# Sania_SCH.net
KiCad netlist of a schematic drawn in EAGLE
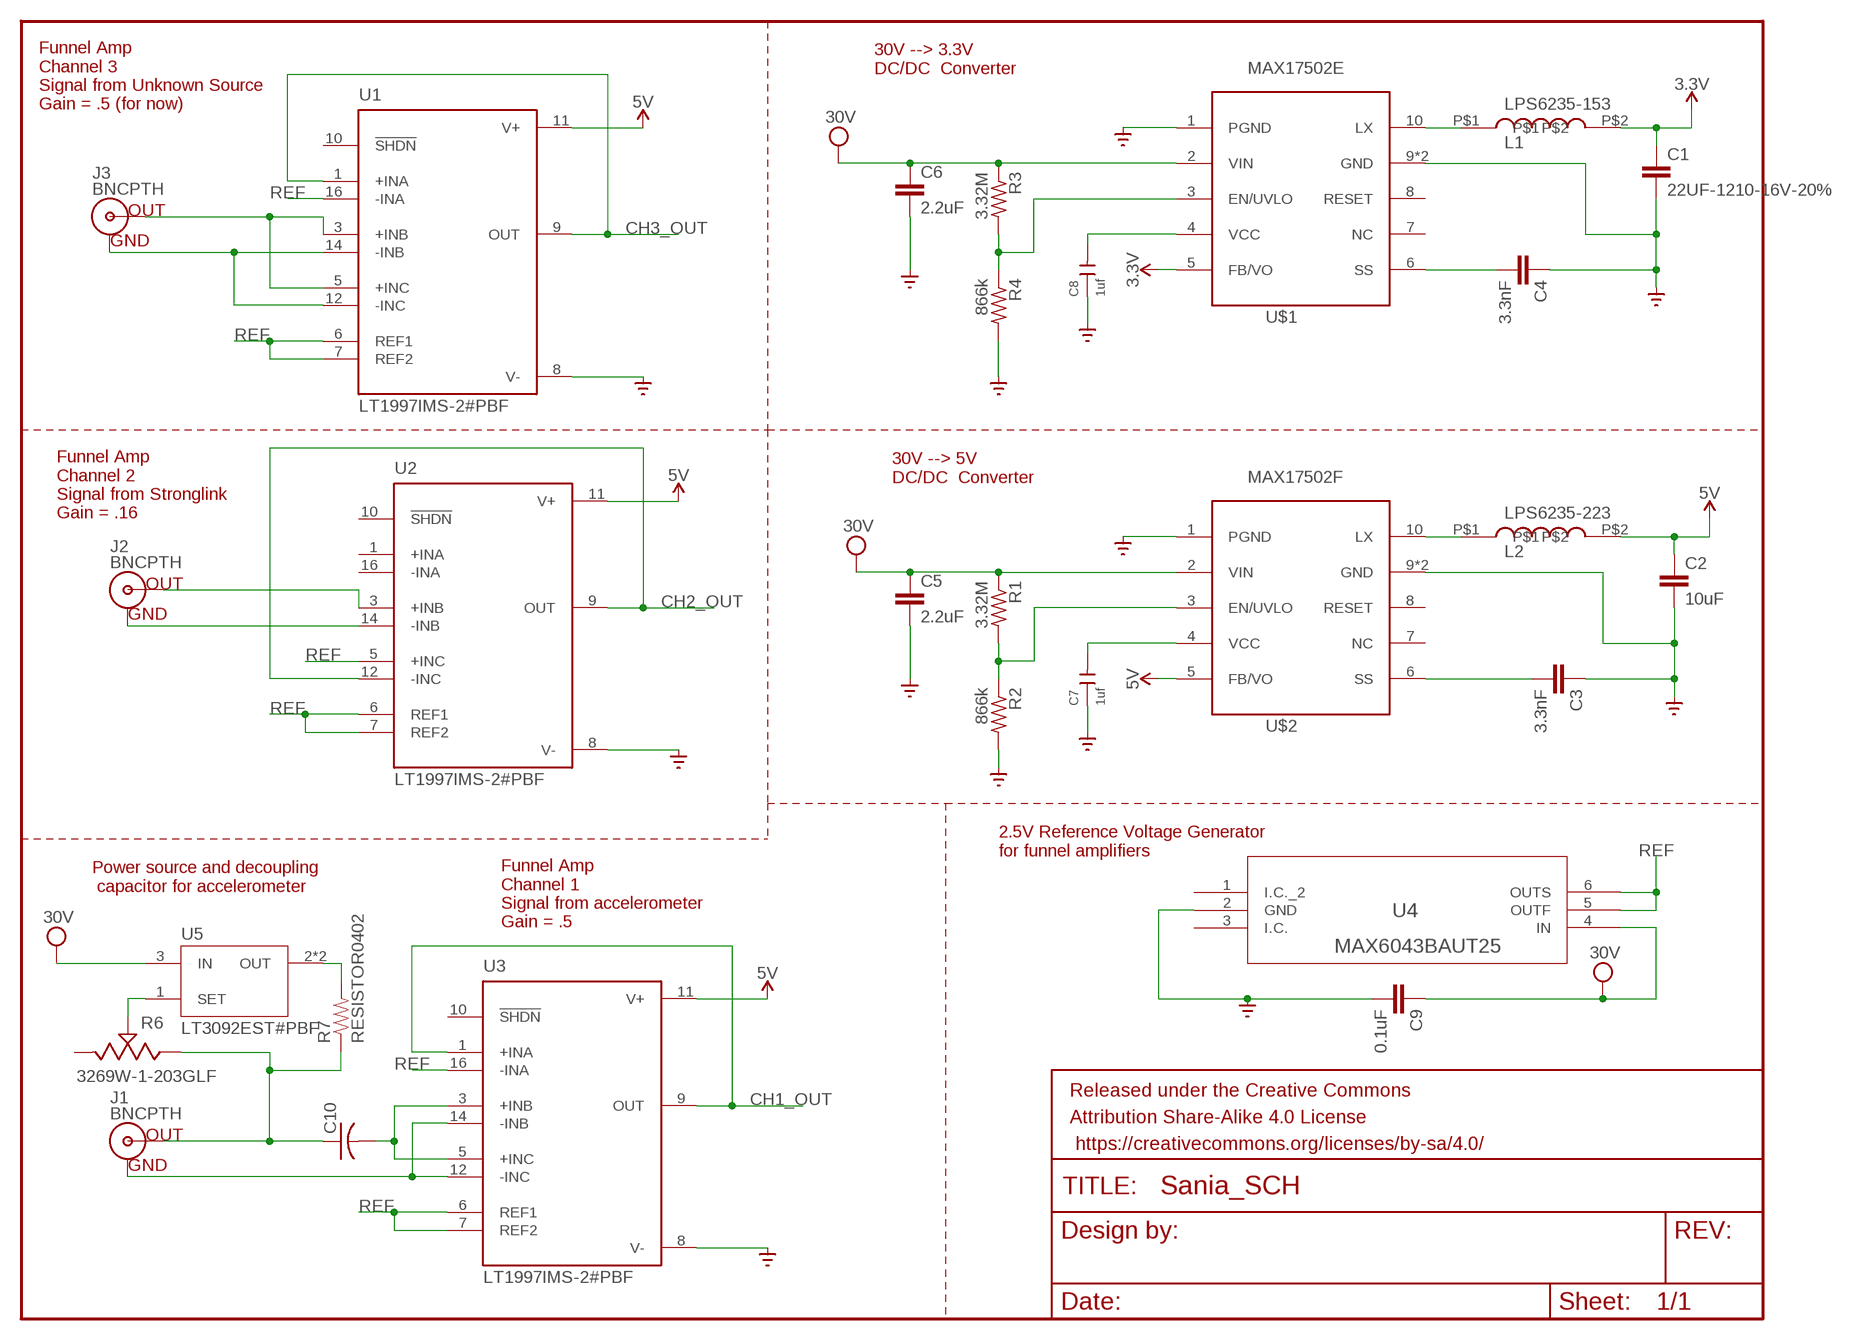
[diagram p0: schematic, sheet 1]

(export (version "E")
  (design (tool "Eeschema 10.0.6"))
  (components
    (comp (ref "C1")
      (value "22UF-1210-16V-20%")
      (footprint "eagle-import:1210")
      (libsource (lib "eagle-import") (part "22UF-1210-16V-20%"))
    )
    (comp (ref "C2")
      (value "10uF")
      (footprint "eagle-import:1210")
      (libsource (lib "eagle-import") (part "10UF-1210-50V-20%"))
    )
    (comp (ref "C3")
      (value "3.3nF")
      (footprint "eagle-import:0603")
      (libsource (lib "eagle-import") (part "3.3NF-0603-100V-10%"))
    )
    (comp (ref "C4")
      (value "3.3nF")
      (footprint "eagle-import:0603")
      (libsource (lib "eagle-import") (part "3.3NF-0603-100V-10%"))
    )
    (comp (ref "C5")
      (value "2.2uF")
      (footprint "eagle-import:1206")
      (libsource (lib "eagle-import") (part "2.2UF-1206-50V-10%"))
    )
    (comp (ref "C6")
      (value "2.2uF")
      (footprint "eagle-import:1206")
      (libsource (lib "eagle-import") (part "2.2UF-1206-50V-10%"))
    )
    (comp (ref "C7")
      (value "1uf")
      (footprint "eagle-import:C0805")
      (fields (field (name "MPN") "CC0805KKX7R8BB105"))
      (libsource (lib "eagle-import") (part "CERAMIC-1UF-25V-10%-X7R(0805)"))
    )
    (comp (ref "C8")
      (value "1uf")
      (footprint "eagle-import:C0805")
      (fields (field (name "MPN") "CC0805KKX7R8BB105"))
      (libsource (lib "eagle-import") (part "CERAMIC-1UF-25V-10%-X7R(0805)"))
    )
    (comp (ref "C9")
      (value "0.1uF")
      (footprint "eagle-import:0603")
      (libsource (lib "eagle-import") (part "0.1UF-0603-25V-(+80/-20%)"))
    )
    (comp (ref "C10")
      (value "C-USC0603")
      (footprint "eagle-import:C0603")
      (libsource (lib "eagle-import") (part "C-USC0603"))
    )
    (comp (ref "FRAME1")
      (value "FRAME-LETTER")
      (footprint "eagle-import:CREATIVE_COMMONS")
      (libsource (lib "eagle-import") (part "FRAME-LETTER"))
    )
    (comp (ref "J1")
      (value "BNCPTH")
      (footprint "eagle-import:BNC")
      (libsource (lib "eagle-import") (part "BNCPTH"))
    )
    (comp (ref "J2")
      (value "BNCPTH")
      (footprint "eagle-import:BNC")
      (libsource (lib "eagle-import") (part "BNCPTH"))
    )
    (comp (ref "J3")
      (value "BNCPTH")
      (footprint "eagle-import:BNC")
      (libsource (lib "eagle-import") (part "BNCPTH"))
    )
    (comp (ref "L1")
      (value "LPS6235-153")
      (footprint "eagle-import:LPS6235")
      (libsource (lib "eagle-import") (part "LPS6235"))
    )
    (comp (ref "L2")
      (value "LPS6235-223")
      (footprint "eagle-import:LPS6235")
      (libsource (lib "eagle-import") (part "LPS6235"))
    )
    (comp (ref "R1")
      (value "3.32M")
      (footprint "eagle-import:R0805")
      (libsource (lib "eagle-import") (part "R-US_R0805"))
    )
    (comp (ref "R2")
      (value "866k")
      (footprint "eagle-import:R0805")
      (libsource (lib "eagle-import") (part "R-US_R0805"))
    )
    (comp (ref "R3")
      (value "3.32M")
      (footprint "eagle-import:R0805")
      (libsource (lib "eagle-import") (part "R-US_R0805"))
    )
    (comp (ref "R4")
      (value "866k")
      (footprint "eagle-import:R0805")
      (libsource (lib "eagle-import") (part "R-US_R0805"))
    )
    (comp (ref "R6")
      (value "3269W-1-203GLF")
      (footprint "eagle-import:3269W-1-203GLF")
      (fields (field (name "MANUFACTURER") "Bourns Inc.") (field (name "CREATED_BY") "PCBLayout.com"))
      (libsource (lib "eagle-import") (part "3269W-1-203GLF"))
    )
    (comp (ref "R7")
      (value "RESISTOR0402")
      (footprint "eagle-import:0402-RES")
      (libsource (lib "eagle-import") (part "RESISTOR0402"))
    )
    (comp (ref "U$1")
      (value "MAX17502E")
      (footprint "eagle-import:SON50P200X300X80-11T90X200N")
      (libsource (lib "eagle-import") (part "MAX17502"))
    )
    (comp (ref "U$2")
      (value "MAX17502F")
      (footprint "eagle-import:SON50P200X300X80-11T90X200N")
      (libsource (lib "eagle-import") (part "MAX17502"))
    )
    (comp (ref "U1")
      (value "LT1997IMS-2#PBF")
      (footprint "eagle-import:SOP50P490X110-12N")
      (fields (field (name "MF") "Analog Devices"))
      (libsource (lib "eagle-import") (part "LT1997IMS-2#PBF"))
    )
    (comp (ref "U2")
      (value "LT1997IMS-2#PBF")
      (footprint "eagle-import:SOP50P490X110-12N")
      (fields (field (name "MF") "Analog Devices"))
      (libsource (lib "eagle-import") (part "LT1997IMS-2#PBF"))
    )
    (comp (ref "U3")
      (value "LT1997IMS-2#PBF")
      (footprint "eagle-import:SOP50P490X110-12N")
      (fields (field (name "MF") "Analog Devices"))
      (libsource (lib "eagle-import") (part "LT1997IMS-2#PBF"))
    )
    (comp (ref "U4")
      (value "MAX6043BAUT25")
      (footprint "eagle-import:21-0058I")
      (fields (field (name "MF") "Maxim Integrated"))
      (libsource (lib "eagle-import") (part "MAX6043BAUT25"))
    )
    (comp (ref "U5")
      (value "LT3092EST#PBF")
      (footprint "eagle-import:IC_LT3092EST#PBF")
      (fields (field (name "MF") "Analog Devices"))
      (libsource (lib "eagle-import") (part "LT3092EST#PBF"))
    )
  )
  (nets
    (net (code "1") (name "/CH1_OUT") (class "Default")
      (node (ref "U3") (pin "1") (pinfunction "+INA_1") (pintype "input"))
      (node (ref "U3") (pin "9") (pinfunction "OUT_9") (pintype "output"))
    )
    (net (code "2") (name "/CH2_OUT") (class "Default")
      (node (ref "U2") (pin "12") (pinfunction "-INC_12") (pintype "input"))
      (node (ref "U2") (pin "9") (pinfunction "OUT_9") (pintype "output"))
    )
    (net (code "3") (name "/CH3_OUT") (class "Default")
      (node (ref "U1") (pin "1") (pinfunction "+INA_1") (pintype "input"))
      (node (ref "U1") (pin "9") (pinfunction "OUT_9") (pintype "output"))
    )
    (net (code "4") (name "/REF") (class "Default")
      (node (ref "U1") (pin "16") (pinfunction "-INA_16") (pintype "input"))
      (node (ref "U1") (pin "6") (pinfunction "REF1_6") (pintype "input"))
      (node (ref "U1") (pin "7") (pinfunction "REF2_7") (pintype "input"))
      (node (ref "U2") (pin "5") (pinfunction "+INC_5") (pintype "input"))
      (node (ref "U2") (pin "6") (pinfunction "REF1_6") (pintype "input"))
      (node (ref "U2") (pin "7") (pinfunction "REF2_7") (pintype "input"))
      (node (ref "U3") (pin "16") (pinfunction "-INA_16") (pintype "input"))
      (node (ref "U3") (pin "6") (pinfunction "REF1_6") (pintype "input"))
      (node (ref "U3") (pin "7") (pinfunction "REF2_7") (pintype "input"))
      (node (ref "U4") (pin "5") (pinfunction "OUTF_5") (pintype "output"))
      (node (ref "U4") (pin "6") (pinfunction "OUTS_6") (pintype "output"))
    )
    (net (code "5") (name "3.3V") (class "Default")
      (node (ref "C1") (pin "1") (pinfunction "1_1") (pintype "passive"))
      (node (ref "L1") (pin "P$2") (pinfunction "P$2_P$2") (pintype "bidirectional"))
      (node (ref "U$1") (pin "5") (pinfunction "FB/VO_5") (pintype "bidirectional"))
    )
    (net (code "6") (name "5V") (class "Default")
      (node (ref "C2") (pin "1") (pinfunction "1_1") (pintype "passive"))
      (node (ref "L2") (pin "P$2") (pinfunction "P$2_P$2") (pintype "bidirectional"))
      (node (ref "U$2") (pin "5") (pinfunction "FB/VO_5") (pintype "bidirectional"))
      (node (ref "U1") (pin "11") (pinfunction "V+_11") (pintype "power_in"))
      (node (ref "U2") (pin "11") (pinfunction "V+_11") (pintype "power_in"))
      (node (ref "U3") (pin "11") (pinfunction "V+_11") (pintype "power_in"))
    )
    (net (code "7") (name "30V") (class "Default")
      (node (ref "C5") (pin "1") (pinfunction "1_1") (pintype "passive"))
      (node (ref "C6") (pin "1") (pinfunction "1_1") (pintype "passive"))
      (node (ref "C9") (pin "1") (pinfunction "1_1") (pintype "passive"))
      (node (ref "R1") (pin "1") (pinfunction "1_1") (pintype "passive"))
      (node (ref "R3") (pin "1") (pinfunction "1_1") (pintype "passive"))
      (node (ref "U$1") (pin "2") (pinfunction "VIN_2") (pintype "bidirectional"))
      (node (ref "U$2") (pin "2") (pinfunction "VIN_2") (pintype "bidirectional"))
      (node (ref "U4") (pin "4") (pinfunction "IN_4") (pintype "input"))
      (node (ref "U5") (pin "3") (pinfunction "IN_3") (pintype "input"))
    )
    (net (code "8") (name "Net-(J1-OUT)") (class "Default")
      (node (ref "C10") (pin "1") (pinfunction "1_1") (pintype "passive"))
      (node (ref "J1") (pin "S") (pinfunction "OUT_S") (pintype "bidirectional"))
      (node (ref "R6") (pin "3") (pinfunction "3_3") (pintype "passive"))
      (node (ref "R7") (pin "1") (pinfunction "1_1") (pintype "passive"))
    )
    (net (code "9") (name "Net-(J2-OUT)") (class "Default")
      (node (ref "J2") (pin "S") (pinfunction "OUT_S") (pintype "bidirectional"))
      (node (ref "U2") (pin "3") (pinfunction "+INB_3") (pintype "input"))
    )
    (net (code "10") (name "Net-(J3-OUT)") (class "Default")
      (node (ref "J3") (pin "S") (pinfunction "OUT_S") (pintype "bidirectional"))
      (node (ref "U1") (pin "3") (pinfunction "+INB_3") (pintype "input"))
      (node (ref "U1") (pin "5") (pinfunction "+INC_5") (pintype "input"))
    )
    (net (code "11") (name "Net-(R7-Pad2)") (class "Default")
      (node (ref "R7") (pin "2") (pinfunction "2_2") (pintype "passive"))
      (node (ref "U5") (pin "2") (pinfunction "OUT_2") (pintype "output"))
      (node (ref "U5") (pin "4") (pinfunction "OUT_4") (pintype "output"))
    )
    (net (code "12") (name "Net-(U$1-EN{slash}UVLO)") (class "Default")
      (node (ref "R3") (pin "2") (pinfunction "2_2") (pintype "passive"))
      (node (ref "R4") (pin "1") (pinfunction "1_1") (pintype "passive"))
      (node (ref "U$1") (pin "3") (pinfunction "EN/UVLO_3") (pintype "bidirectional"))
    )
    (net (code "13") (name "Net-(U$1-LX)") (class "Default")
      (node (ref "L1") (pin "P$1") (pinfunction "P$1_P$1") (pintype "bidirectional"))
      (node (ref "U$1") (pin "10") (pinfunction "LX_10") (pintype "bidirectional"))
    )
    (net (code "14") (name "Net-(U$1-SS)") (class "Default")
      (node (ref "C4") (pin "2") (pinfunction "2_2") (pintype "passive"))
      (node (ref "U$1") (pin "6") (pinfunction "SS_6") (pintype "bidirectional"))
    )
    (net (code "15") (name "Net-(U$1-VCC)") (class "Default")
      (node (ref "C8") (pin "2") (pinfunction "2_2") (pintype "passive"))
      (node (ref "U$1") (pin "4") (pinfunction "VCC_4") (pintype "bidirectional"))
    )
    (net (code "16") (name "Net-(U$2-EN{slash}UVLO)") (class "Default")
      (node (ref "R1") (pin "2") (pinfunction "2_2") (pintype "passive"))
      (node (ref "R2") (pin "1") (pinfunction "1_1") (pintype "passive"))
      (node (ref "U$2") (pin "3") (pinfunction "EN/UVLO_3") (pintype "bidirectional"))
    )
    (net (code "17") (name "Net-(U$2-LX)") (class "Default")
      (node (ref "L2") (pin "P$1") (pinfunction "P$1_P$1") (pintype "bidirectional"))
      (node (ref "U$2") (pin "10") (pinfunction "LX_10") (pintype "bidirectional"))
    )
    (net (code "18") (name "Net-(U$2-SS)") (class "Default")
      (node (ref "C3") (pin "2") (pinfunction "2_2") (pintype "passive"))
      (node (ref "U$2") (pin "6") (pinfunction "SS_6") (pintype "bidirectional"))
    )
    (net (code "19") (name "Net-(U$2-VCC)") (class "Default")
      (node (ref "C7") (pin "2") (pinfunction "2_2") (pintype "passive"))
      (node (ref "U$2") (pin "4") (pinfunction "VCC_4") (pintype "bidirectional"))
    )
    (net (code "20") (name "Net-(U1--INB)") (class "Default")
      (node (ref "J3") (pin "GND") (pinfunction "GND_GND") (pintype "bidirectional"))
      (node (ref "U1") (pin "12") (pinfunction "-INC_12") (pintype "input"))
      (node (ref "U1") (pin "14") (pinfunction "-INB_14") (pintype "input"))
    )
    (net (code "21") (name "Net-(U2--INB)") (class "Default")
      (node (ref "J2") (pin "GND") (pinfunction "GND_GND") (pintype "bidirectional"))
      (node (ref "U2") (pin "14") (pinfunction "-INB_14") (pintype "input"))
    )
    (net (code "22") (name "Net-(U3-+INB)") (class "Default")
      (node (ref "C10") (pin "2") (pinfunction "2_2") (pintype "passive"))
      (node (ref "U3") (pin "3") (pinfunction "+INB_3") (pintype "input"))
      (node (ref "U3") (pin "5") (pinfunction "+INC_5") (pintype "input"))
    )
    (net (code "23") (name "Net-(U3--INB)") (class "Default")
      (node (ref "J1") (pin "GND") (pinfunction "GND_GND") (pintype "bidirectional"))
      (node (ref "U3") (pin "12") (pinfunction "-INC_12") (pintype "input"))
      (node (ref "U3") (pin "14") (pinfunction "-INB_14") (pintype "input"))
    )
    (net (code "24") (name "Net-(U5-SET)") (class "Default")
      (node (ref "R6") (pin "2") (pinfunction "2_2") (pintype "passive"))
      (node (ref "U5") (pin "1") (pinfunction "SET_1") (pintype "input"))
    )
    (net (code "25") (name "SUPPLY_BRASTAN_GND_") (class "Default")
      (node (ref "C1") (pin "2") (pinfunction "2_2") (pintype "passive"))
      (node (ref "C2") (pin "2") (pinfunction "2_2") (pintype "passive"))
      (node (ref "C3") (pin "1") (pinfunction "1_1") (pintype "passive"))
      (node (ref "C4") (pin "1") (pinfunction "1_1") (pintype "passive"))
      (node (ref "C5") (pin "2") (pinfunction "2_2") (pintype "passive"))
      (node (ref "C6") (pin "2") (pinfunction "2_2") (pintype "passive"))
      (node (ref "C7") (pin "1") (pinfunction "1_1") (pintype "passive"))
      (node (ref "C8") (pin "1") (pinfunction "1_1") (pintype "passive"))
      (node (ref "C9") (pin "2") (pinfunction "2_2") (pintype "passive"))
      (node (ref "R2") (pin "2") (pinfunction "2_2") (pintype "passive"))
      (node (ref "R4") (pin "2") (pinfunction "2_2") (pintype "passive"))
      (node (ref "U$1") (pin "1") (pinfunction "PGND_1") (pintype "bidirectional"))
      (node (ref "U$1") (pin "11") (pinfunction "GND_11") (pintype "bidirectional"))
      (node (ref "U$1") (pin "9") (pinfunction "GND_9") (pintype "bidirectional"))
      (node (ref "U$2") (pin "1") (pinfunction "PGND_1") (pintype "bidirectional"))
      (node (ref "U$2") (pin "11") (pinfunction "GND_11") (pintype "bidirectional"))
      (node (ref "U$2") (pin "9") (pinfunction "GND_9") (pintype "bidirectional"))
      (node (ref "U1") (pin "8") (pinfunction "V-_8") (pintype "power_in"))
      (node (ref "U2") (pin "8") (pinfunction "V-_8") (pintype "power_in"))
      (node (ref "U3") (pin "8") (pinfunction "V-_8") (pintype "power_in"))
      (node (ref "U4") (pin "2") (pinfunction "GND_2") (pintype "power_in"))
    )
    (net (code "26") (name "unconnected-(R6-Pad1)") (class "Default")
      (node (ref "R6") (pin "1") (pinfunction "1_1") (pintype "passive"))
    )
    (net (code "27") (name "unconnected-(U$1-NC-Pad7)") (class "Default")
      (node (ref "U$1") (pin "7") (pinfunction "NC_7") (pintype "bidirectional"))
    )
    (net (code "28") (name "unconnected-(U$1-RESET-Pad8)") (class "Default")
      (node (ref "U$1") (pin "8") (pinfunction "RESET_8") (pintype "bidirectional"))
    )
    (net (code "29") (name "unconnected-(U$2-NC-Pad7)") (class "Default")
      (node (ref "U$2") (pin "7") (pinfunction "NC_7") (pintype "bidirectional"))
    )
    (net (code "30") (name "unconnected-(U$2-RESET-Pad8)") (class "Default")
      (node (ref "U$2") (pin "8") (pinfunction "RESET_8") (pintype "bidirectional"))
    )
    (net (code "31") (name "unconnected-(U1-~{SHDN}-Pad10)") (class "Default")
      (node (ref "U1") (pin "10") (pinfunction "~{SHDN}_10") (pintype "input"))
    )
    (net (code "32") (name "unconnected-(U2-+INA-Pad1)") (class "Default")
      (node (ref "U2") (pin "1") (pinfunction "+INA_1") (pintype "input"))
    )
    (net (code "33") (name "unconnected-(U2--INA-Pad16)") (class "Default")
      (node (ref "U2") (pin "16") (pinfunction "-INA_16") (pintype "input"))
    )
    (net (code "34") (name "unconnected-(U2-~{SHDN}-Pad10)") (class "Default")
      (node (ref "U2") (pin "10") (pinfunction "~{SHDN}_10") (pintype "input"))
    )
    (net (code "35") (name "unconnected-(U3-~{SHDN}-Pad10)") (class "Default")
      (node (ref "U3") (pin "10") (pinfunction "~{SHDN}_10") (pintype "input"))
    )
    (net (code "36") (name "unconnected-(U4-I.C.-Pad3)") (class "Default")
      (node (ref "U4") (pin "3") (pinfunction "I.C._3") (pintype "passive"))
    )
    (net (code "37") (name "unconnected-(U4-I.C._2-Pad1)") (class "Default")
      (node (ref "U4") (pin "1") (pinfunction "I.C._2_1") (pintype "passive"))
    )
  )
)
